# 06-LASERCONTROL.net
KiCad netlist of a schematic drawn in Altium Designer
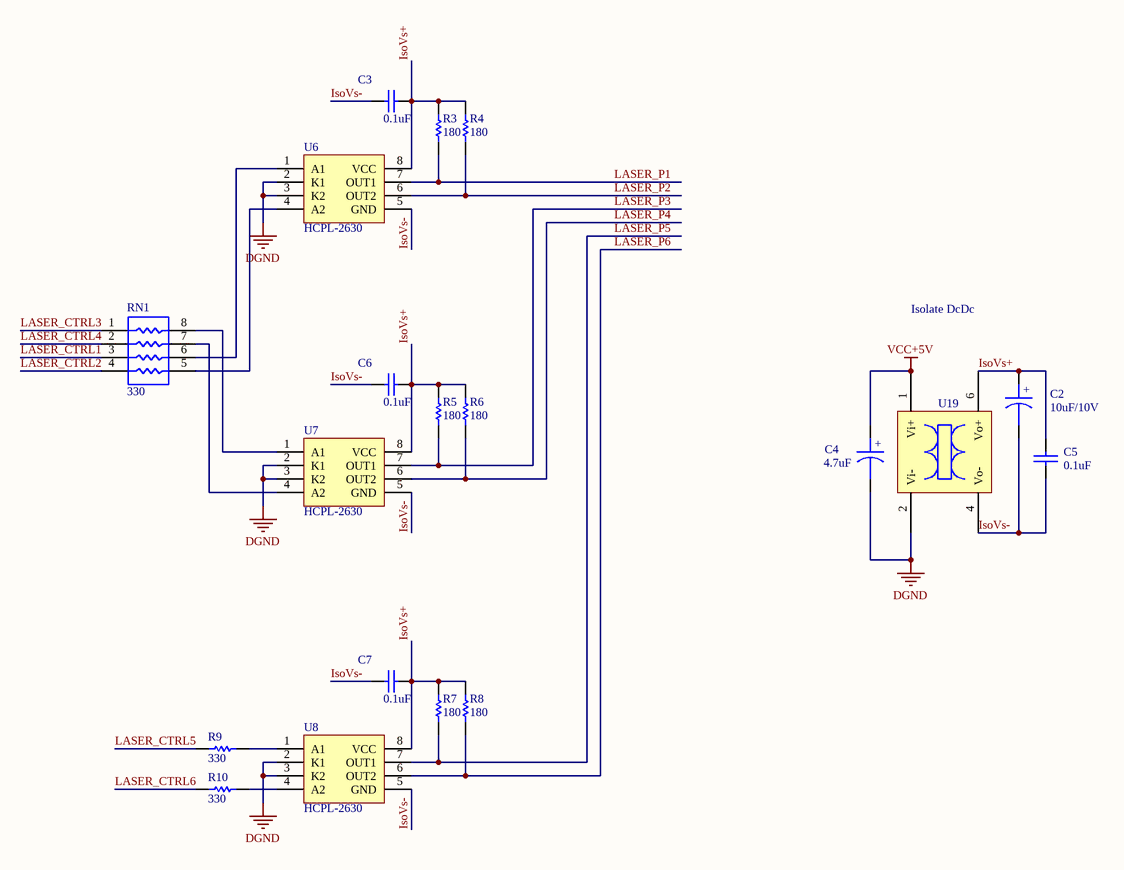
[diagram p0: 06-LASERCONTROL.SchDoc]

(export (version "E")
  (design (tool "Eeschema 10.0.6"))
  (components
    (comp (ref "C2")
      (value "10uF/10V")
      (footprint "CC3225-1210")
      (description "Capacitor")
      (libsource (lib "*") (part "CAPACITOR POL"))
    )
    (comp (ref "C3")
      (value "0.1uF")
      (footprint "CC2012-0805")
      (description "Capacitor")
      (fields (field (name "PUBLISHER") "Altium Limited"))
      (libsource (lib "*") (part "Cap"))
    )
    (comp (ref "C4")
      (value "4.7uF")
      (footprint "CC3225-1210")
      (description "Capacitor")
      (libsource (lib "*") (part "CAPACITOR POL"))
    )
    (comp (ref "C5")
      (value "0.1uF")
      (footprint "0805-X")
      (description "Capacitor")
      (libsource (lib "*") (part "CAP"))
    )
    (comp (ref "C6")
      (value "0.1uF")
      (footprint "CC2012-0805")
      (description "Capacitor")
      (fields (field (name "PUBLISHER") "Altium Limited"))
      (libsource (lib "*") (part "Cap"))
    )
    (comp (ref "C7")
      (value "0.1uF")
      (footprint "CC2012-0805")
      (description "Capacitor")
      (fields (field (name "PUBLISHER") "Altium Limited"))
      (libsource (lib "*") (part "Cap"))
    )
    (comp (ref "R3")
      (value "180")
      (footprint "CR2012-0805")
      (description "Resistor")
      (fields (field (name "PUBLISHER") "Altium Limited"))
      (libsource (lib "*") (part "Res1"))
    )
    (comp (ref "R4")
      (value "180")
      (footprint "CR2012-0805")
      (description "Resistor")
      (fields (field (name "PUBLISHER") "Altium Limited"))
      (libsource (lib "*") (part "Res1"))
    )
    (comp (ref "R5")
      (value "180")
      (footprint "CR2012-0805")
      (description "Resistor")
      (fields (field (name "PUBLISHER") "Altium Limited"))
      (libsource (lib "*") (part "Res1"))
    )
    (comp (ref "R6")
      (value "180")
      (footprint "CR2012-0805")
      (description "Resistor")
      (fields (field (name "PUBLISHER") "Altium Limited"))
      (libsource (lib "*") (part "Res1"))
    )
    (comp (ref "R7")
      (value "180")
      (footprint "CR2012-0805")
      (description "Resistor")
      (fields (field (name "PUBLISHER") "Altium Limited"))
      (libsource (lib "*") (part "Res1"))
    )
    (comp (ref "R8")
      (value "180")
      (footprint "CR2012-0805")
      (description "Resistor")
      (fields (field (name "PUBLISHER") "Altium Limited"))
      (libsource (lib "*") (part "Res1"))
    )
    (comp (ref "R9")
      (value "330")
      (footprint "0805")
      (description "Resistor")
      (fields (field (name "PUBLISHER") "Altium Limited"))
      (libsource (lib "*") (part "Res1"))
    )
    (comp (ref "R10")
      (value "330")
      (footprint "0805")
      (description "Resistor")
      (fields (field (name "PUBLISHER") "Altium Limited"))
      (libsource (lib "*") (part "Res1"))
    )
    (comp (ref "RN1")
      (value "330")
      (footprint "CRP4.1608")
      (description "Resistor Array,include 4 resistor in one chip")
      (libsource (lib "电子元器件") (part "RN4"))
    )
    (comp (ref "U6") (value "HCPL-2630") (footprint "SO-G8/Z10.8") (libsource (lib "*") (part "HCPL-2630")))
    (comp (ref "U7") (value "HCPL-2630") (footprint "SO-G8/Z10.8") (libsource (lib "*") (part "HCPL-2630")))
    (comp (ref "U8") (value "HCPL-2630") (footprint "SO-G8/Z10.8") (libsource (lib "*") (part "HCPL-2630")))
    (comp (ref "U19") (value "Isolate DcDc") (footprint "IB0505LS") (libsource (lib "*") (part "MY_I_DC_DC")))
  )
  (nets
    (net (code "1") (name "/IsoVs+") (class "Default")
      (node (ref "C2") (pin "1") (pinfunction "1_1") (pintype "passive"))
      (node (ref "C3") (pin "1") (pinfunction "1_1") (pintype "passive"))
      (node (ref "C5") (pin "1") (pinfunction "1_1") (pintype "passive"))
      (node (ref "C6") (pin "1") (pinfunction "1_1") (pintype "passive"))
      (node (ref "C7") (pin "1") (pinfunction "1_1") (pintype "passive"))
      (node (ref "R3") (pin "1") (pinfunction "1_1") (pintype "passive"))
      (node (ref "R4") (pin "1") (pinfunction "1_1") (pintype "passive"))
      (node (ref "R5") (pin "1") (pinfunction "1_1") (pintype "passive"))
      (node (ref "R6") (pin "1") (pinfunction "1_1") (pintype "passive"))
      (node (ref "R7") (pin "1") (pinfunction "1_1") (pintype "passive"))
      (node (ref "R8") (pin "1") (pinfunction "1_1") (pintype "passive"))
      (node (ref "U19") (pin "6") (pinfunction "Vo+_6") (pintype "passive"))
      (node (ref "U6") (pin "8") (pinfunction "VCC_8") (pintype "power_in"))
      (node (ref "U7") (pin "8") (pinfunction "VCC_8") (pintype "power_in"))
      (node (ref "U8") (pin "8") (pinfunction "VCC_8") (pintype "power_in"))
    )
    (net (code "2") (name "/IsoVs-") (class "Default")
      (node (ref "C2") (pin "2") (pinfunction "2_2") (pintype "passive"))
      (node (ref "C3") (pin "2") (pinfunction "2_2") (pintype "passive"))
      (node (ref "C5") (pin "2") (pinfunction "2_2") (pintype "passive"))
      (node (ref "C6") (pin "2") (pinfunction "2_2") (pintype "passive"))
      (node (ref "C7") (pin "2") (pinfunction "2_2") (pintype "passive"))
      (node (ref "U19") (pin "4") (pinfunction "Vo-_4") (pintype "passive"))
      (node (ref "U6") (pin "5") (pinfunction "GND_5") (pintype "power_in"))
      (node (ref "U7") (pin "5") (pinfunction "GND_5") (pintype "power_in"))
      (node (ref "U8") (pin "5") (pinfunction "GND_5") (pintype "power_in"))
    )
    (net (code "3") (name "/LASER_CTRL1") (class "Default")
      (node (ref "RN1") (pin "3") (pinfunction "3_3") (pintype "passive"))
    )
    (net (code "4") (name "/LASER_CTRL2") (class "Default")
      (node (ref "RN1") (pin "4") (pinfunction "4_4") (pintype "passive"))
    )
    (net (code "5") (name "/LASER_CTRL3") (class "Default")
      (node (ref "RN1") (pin "1") (pinfunction "1_1") (pintype "passive"))
    )
    (net (code "6") (name "/LASER_CTRL4") (class "Default")
      (node (ref "RN1") (pin "2") (pinfunction "2_2") (pintype "passive"))
    )
    (net (code "7") (name "/LASER_CTRL5") (class "Default")
      (node (ref "R9") (pin "1") (pinfunction "1_1") (pintype "passive"))
    )
    (net (code "8") (name "/LASER_CTRL6") (class "Default")
      (node (ref "R10") (pin "1") (pinfunction "1_1") (pintype "passive"))
    )
    (net (code "9") (name "/LASER_P1") (class "Default")
      (node (ref "R3") (pin "2") (pinfunction "2_2") (pintype "passive"))
      (node (ref "U6") (pin "7") (pinfunction "OUT1_7") (pintype "open_collector"))
    )
    (net (code "10") (name "/LASER_P2") (class "Default")
      (node (ref "R4") (pin "2") (pinfunction "2_2") (pintype "passive"))
      (node (ref "U6") (pin "6") (pinfunction "OUT2_6") (pintype "open_collector"))
    )
    (net (code "11") (name "/LASER_P3") (class "Default")
      (node (ref "R5") (pin "2") (pinfunction "2_2") (pintype "passive"))
      (node (ref "U7") (pin "7") (pinfunction "OUT1_7") (pintype "open_collector"))
    )
    (net (code "12") (name "/LASER_P4") (class "Default")
      (node (ref "R6") (pin "2") (pinfunction "2_2") (pintype "passive"))
      (node (ref "U7") (pin "6") (pinfunction "OUT2_6") (pintype "open_collector"))
    )
    (net (code "13") (name "/LASER_P5") (class "Default")
      (node (ref "R7") (pin "2") (pinfunction "2_2") (pintype "passive"))
      (node (ref "U8") (pin "7") (pinfunction "OUT1_7") (pintype "open_collector"))
    )
    (net (code "14") (name "/LASER_P6") (class "Default")
      (node (ref "R8") (pin "2") (pinfunction "2_2") (pintype "passive"))
      (node (ref "U8") (pin "6") (pinfunction "OUT2_6") (pintype "open_collector"))
    )
    (net (code "15") (name "DGND") (class "Default")
      (node (ref "C4") (pin "2") (pinfunction "2_2") (pintype "passive"))
      (node (ref "U19") (pin "2") (pinfunction "Vi-_2") (pintype "passive"))
      (node (ref "U6") (pin "2") (pinfunction "K1_2") (pintype "passive"))
      (node (ref "U6") (pin "3") (pinfunction "K2_3") (pintype "passive"))
      (node (ref "U7") (pin "2") (pinfunction "K1_2") (pintype "passive"))
      (node (ref "U7") (pin "3") (pinfunction "K2_3") (pintype "passive"))
      (node (ref "U8") (pin "2") (pinfunction "K1_2") (pintype "passive"))
      (node (ref "U8") (pin "3") (pinfunction "K2_3") (pintype "passive"))
    )
    (net (code "16") (name "Net-(U6-A1)") (class "Default")
      (node (ref "RN1") (pin "6") (pinfunction "6_6") (pintype "passive"))
      (node (ref "U6") (pin "1") (pinfunction "A1_1") (pintype "passive"))
    )
    (net (code "17") (name "Net-(U6-A2)") (class "Default")
      (node (ref "RN1") (pin "5") (pinfunction "5_5") (pintype "passive"))
      (node (ref "U6") (pin "4") (pinfunction "A2_4") (pintype "passive"))
    )
    (net (code "18") (name "Net-(U7-A1)") (class "Default")
      (node (ref "RN1") (pin "8") (pinfunction "8_8") (pintype "passive"))
      (node (ref "U7") (pin "1") (pinfunction "A1_1") (pintype "passive"))
    )
    (net (code "19") (name "Net-(U7-A2)") (class "Default")
      (node (ref "RN1") (pin "7") (pinfunction "7_7") (pintype "passive"))
      (node (ref "U7") (pin "4") (pinfunction "A2_4") (pintype "passive"))
    )
    (net (code "20") (name "Net-(U8-A1)") (class "Default")
      (node (ref "R9") (pin "2") (pinfunction "2_2") (pintype "passive"))
      (node (ref "U8") (pin "1") (pinfunction "A1_1") (pintype "passive"))
    )
    (net (code "21") (name "Net-(U8-A2)") (class "Default")
      (node (ref "R10") (pin "2") (pinfunction "2_2") (pintype "passive"))
      (node (ref "U8") (pin "4") (pinfunction "A2_4") (pintype "passive"))
    )
    (net (code "22") (name "VCC+5V") (class "Default")
      (node (ref "C4") (pin "1") (pinfunction "1_1") (pintype "passive"))
      (node (ref "U19") (pin "1") (pinfunction "Vi+_1") (pintype "passive"))
    )
  )
)
